# Connectors-MK2-1ch.net
KiCad netlist of a schematic drawn in EAGLE
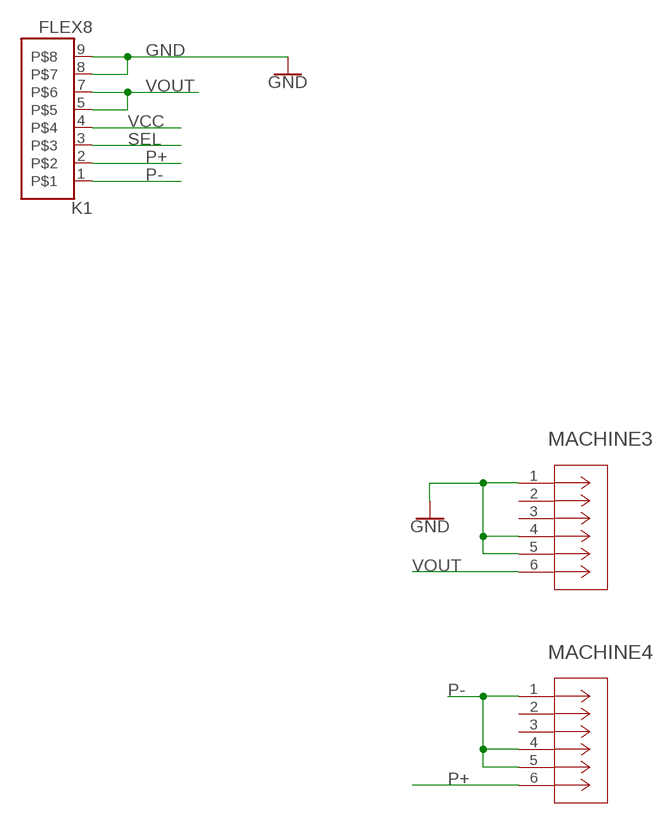
[diagram p0: schematic, sheet 1]

(export (version "E")
  (design (tool "Eeschema 10.0.6"))
  (components
    (comp (ref "K1")
      (value "FLEX8")
      (footprint "eagle-import:FLEX8")
      (libsource (lib "eagle-import") (part "FLEX8"))
    )
    (comp (ref "MACHINE3")
      (value "ACJS-MHDR")
      (footprint "eagle-import:CONN_MHDR_AMP")
      (fields (field (name "COPYRIGHT") "Copyright (C) 2018 Accelerated Designs. All rights reserved"))
      (libsource (lib "eagle-import") (part "ACJS-MHDR"))
    )
    (comp (ref "MACHINE4")
      (value "ACJS-MHDR")
      (footprint "eagle-import:CONN_MHDR_AMP")
      (fields (field (name "COPYRIGHT") "Copyright (C) 2018 Accelerated Designs. All rights reserved"))
      (libsource (lib "eagle-import") (part "ACJS-MHDR"))
    )
  )
  (nets
    (net (code "1") (name "/P+") (class "Default")
      (node (ref "K1") (pin "2") (pinfunction "P$2_2") (pintype "bidirectional"))
      (node (ref "MACHINE4") (pin "6") (pinfunction "6_6") (pintype "passive"))
    )
    (net (code "2") (name "/P-") (class "Default")
      (node (ref "K1") (pin "1") (pinfunction "P$1_1") (pintype "bidirectional"))
      (node (ref "MACHINE4") (pin "1") (pinfunction "1_1") (pintype "passive"))
      (node (ref "MACHINE4") (pin "4") (pinfunction "4_4") (pintype "passive"))
      (node (ref "MACHINE4") (pin "5") (pinfunction "5_5") (pintype "passive"))
    )
    (net (code "3") (name "/SEL") (class "Default")
      (node (ref "K1") (pin "3") (pinfunction "P$3_3") (pintype "bidirectional"))
    )
    (net (code "4") (name "/VCC") (class "Default")
      (node (ref "K1") (pin "4") (pinfunction "P$4_4") (pintype "bidirectional"))
    )
    (net (code "5") (name "/VOUT") (class "Default")
      (node (ref "K1") (pin "5") (pinfunction "P$5_5") (pintype "bidirectional"))
      (node (ref "K1") (pin "7") (pinfunction "P$6_7") (pintype "bidirectional"))
      (node (ref "MACHINE3") (pin "6") (pinfunction "6_6") (pintype "passive"))
    )
    (net (code "6") (name "GND") (class "Default")
      (node (ref "K1") (pin "8") (pinfunction "P$7_8") (pintype "bidirectional"))
      (node (ref "K1") (pin "9") (pinfunction "P$8_9") (pintype "bidirectional"))
      (node (ref "MACHINE3") (pin "1") (pinfunction "1_1") (pintype "passive"))
      (node (ref "MACHINE3") (pin "4") (pinfunction "4_4") (pintype "passive"))
      (node (ref "MACHINE3") (pin "5") (pinfunction "5_5") (pintype "passive"))
    )
    (net (code "7") (name "unconnected-(MACHINE3-Pad2)") (class "Default")
      (node (ref "MACHINE3") (pin "2") (pinfunction "2_2") (pintype "passive"))
    )
    (net (code "8") (name "unconnected-(MACHINE3-Pad3)") (class "Default")
      (node (ref "MACHINE3") (pin "3") (pinfunction "3_3") (pintype "passive"))
    )
    (net (code "9") (name "unconnected-(MACHINE4-Pad2)") (class "Default")
      (node (ref "MACHINE4") (pin "2") (pinfunction "2_2") (pintype "passive"))
    )
    (net (code "10") (name "unconnected-(MACHINE4-Pad3)") (class "Default")
      (node (ref "MACHINE4") (pin "3") (pinfunction "3_3") (pintype "passive"))
    )
  )
)
